# WheeStat5_1d.net
KiCad netlist of a schematic drawn in EAGLE
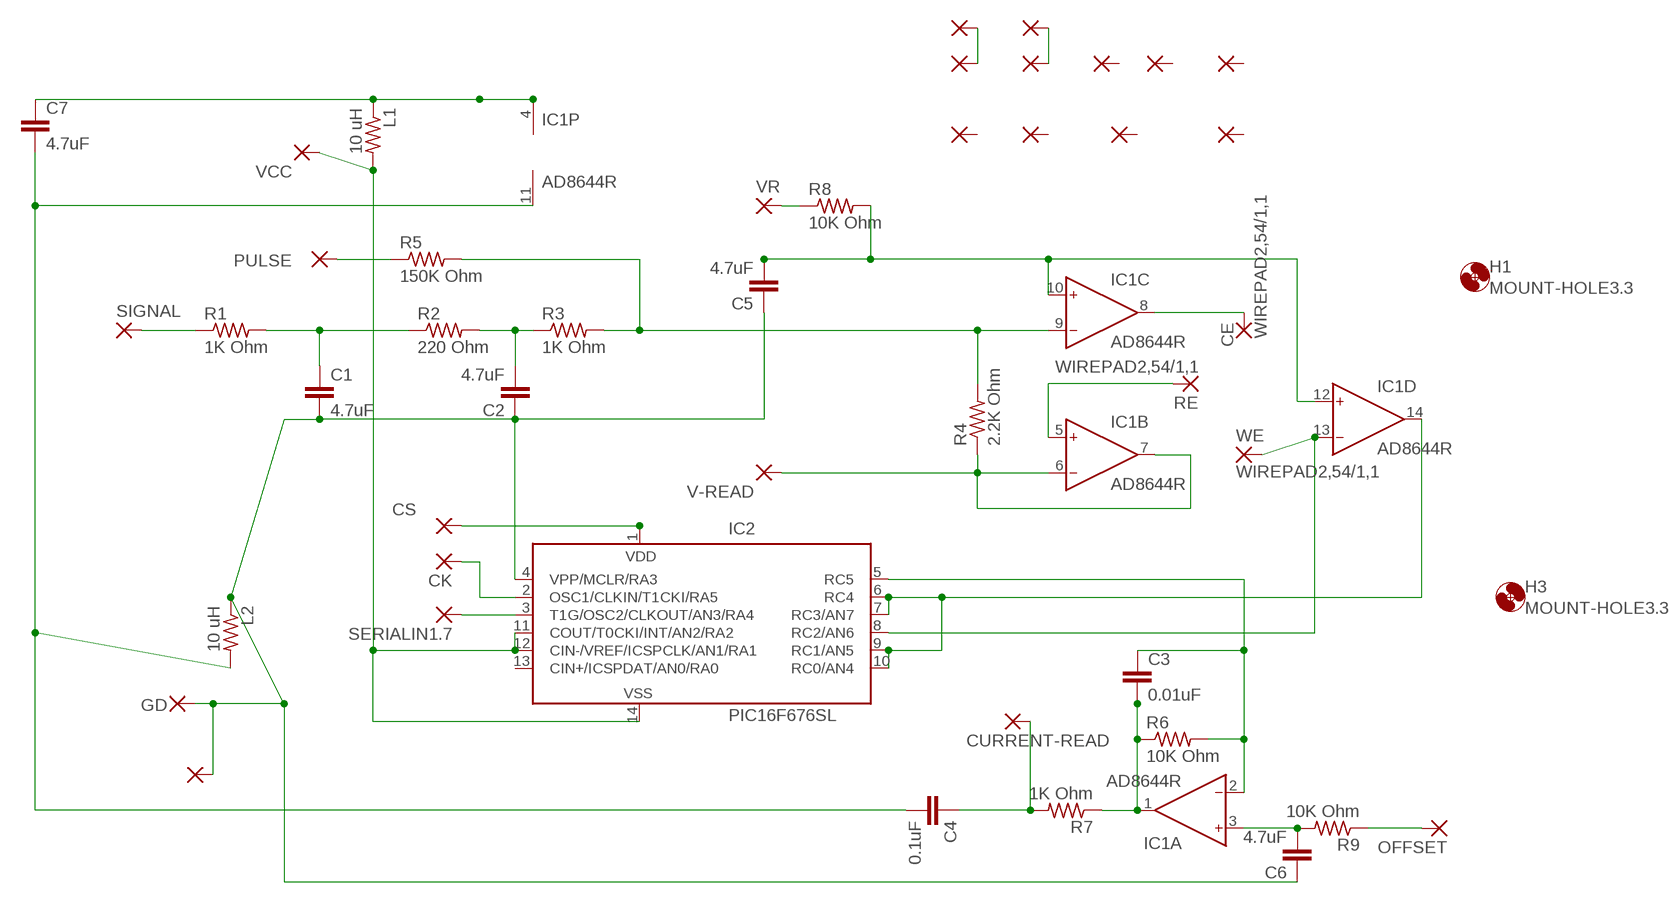
[diagram p0: schematic, sheet 1]

(export (version "E")
  (design (tool "Eeschema 10.0.6"))
  (components
    (comp (ref "1")
      (value "1,6/0,9")
      (footprint "eagle-import:1,6_0,9")
      (libsource (lib "eagle-import") (part "1,6/0,9"))
    )
    (comp (ref "1.1")
      (value "1,6/0,9")
      (footprint "eagle-import:1,6_0,9")
      (libsource (lib "eagle-import") (part "1,6/0,9"))
    )
    (comp (ref "1.2")
      (value "1,6/0,9")
      (footprint "eagle-import:1,6_0,9")
      (libsource (lib "eagle-import") (part "1,6/0,9"))
    )
    (comp (ref "1.3")
      (value "1,6/0,9")
      (footprint "eagle-import:1,6_0,9")
      (libsource (lib "eagle-import") (part "1,6/0,9"))
    )
    (comp (ref "1.4")
      (value "1,6/0,9")
      (footprint "eagle-import:1,6_0,9")
      (libsource (lib "eagle-import") (part "1,6/0,9"))
    )
    (comp (ref "2")
      (value "1,6/0,9")
      (footprint "eagle-import:1,6_0,9")
      (libsource (lib "eagle-import") (part "1,6/0,9"))
    )
    (comp (ref "3")
      (value "1,6/0,9")
      (footprint "eagle-import:1,6_0,9")
      (libsource (lib "eagle-import") (part "1,6/0,9"))
    )
    (comp (ref "4")
      (value "1,6/0,9")
      (footprint "eagle-import:1,6_0,9")
      (libsource (lib "eagle-import") (part "1,6/0,9"))
    )
    (comp (ref "5")
      (value "1,6/0,9")
      (footprint "eagle-import:1,6_0,9")
      (libsource (lib "eagle-import") (part "1,6/0,9"))
    )
    (comp (ref "6")
      (value "1,6/0,9")
      (footprint "eagle-import:1,6_0,9")
      (libsource (lib "eagle-import") (part "1,6/0,9"))
    )
    (comp (ref "7")
      (value "1,6/0,9")
      (footprint "eagle-import:1,6_0,9")
      (libsource (lib "eagle-import") (part "1,6/0,9"))
    )
    (comp (ref "8")
      (value "1,6/0,9")
      (footprint "eagle-import:1,6_0,9")
      (libsource (lib "eagle-import") (part "1,6/0,9"))
    )
    (comp (ref "C1")
      (value "4.7uF")
      (footprint "eagle-import:C1206K")
      (libsource (lib "eagle-import") (part "resistor_C-EUC1206K"))
    )
    (comp (ref "C2")
      (value "4.7uF")
      (footprint "eagle-import:C1206K")
      (libsource (lib "eagle-import") (part "resistor_C-EUC1206K"))
    )
    (comp (ref "C3")
      (value "0.01uF")
      (footprint "eagle-import:C0805")
      (libsource (lib "eagle-import") (part "C-EUC0805"))
    )
    (comp (ref "C4")
      (value "0.1uF")
      (footprint "eagle-import:C1206K")
      (libsource (lib "eagle-import") (part "resistor_C-EUC1206K"))
    )
    (comp (ref "C5")
      (value "4.7uF")
      (footprint "eagle-import:C1206K")
      (libsource (lib "eagle-import") (part "resistor_C-EUC1206K"))
    )
    (comp (ref "C6")
      (value "4.7uF")
      (footprint "eagle-import:C1206K")
      (libsource (lib "eagle-import") (part "resistor_C-EUC1206K"))
    )
    (comp (ref "C7")
      (value "4.7uF")
      (footprint "eagle-import:C1206K")
      (libsource (lib "eagle-import") (part "resistor_C-EUC1206K"))
    )
    (comp (ref "CE")
      (value "WIREPAD2,54/1,1")
      (footprint "eagle-import:2,54_1,1")
      (libsource (lib "eagle-import") (part "WIREPAD2,54/1,1"))
    )
    (comp (ref "CK")
      (value "1,6/0,9")
      (footprint "eagle-import:1,6_0,9")
      (libsource (lib "eagle-import") (part "1,6/0,9"))
    )
    (comp (ref "CS")
      (value "1,6/0,9")
      (footprint "eagle-import:1,6_0,9")
      (libsource (lib "eagle-import") (part "1,6/0,9"))
    )
    (comp (ref "CURRENT-READ")
      (value "1,6/0,9")
      (footprint "eagle-import:1,6_0,9")
      (libsource (lib "eagle-import") (part "1,6/0,9"))
    )
    (comp (ref "GD")
      (value "1,6/0,9")
      (footprint "eagle-import:1,6_0,9")
      (libsource (lib "eagle-import") (part "1,6/0,9"))
    )
    (comp (ref "H1")
      (value "MOUNT-HOLE3.3")
      (footprint "eagle-import:3,3")
      (libsource (lib "eagle-import") (part "MOUNT-HOLE3.3"))
    )
    (comp (ref "H3")
      (value "MOUNT-HOLE3.3")
      (footprint "eagle-import:3,3")
      (libsource (lib "eagle-import") (part "MOUNT-HOLE3.3"))
    )
    (comp (ref "IC1")
      (value "AD8644R")
      (footprint "eagle-import:SO14")
      (fields (field (name "MF") "ALTERA CORPORATION") (field (name "MPN") "AD8644ARZ"))
      (libsource (lib "eagle-import") (part "AD8644R"))
    )
    (comp (ref "IC2")
      (value "PIC16F676SL")
      (footprint "eagle-import:SO-14")
      (fields (field (name "MF") "MICROCHIP") (field (name "MPN") "PIC16F676-I/SL"))
      (libsource (lib "eagle-import") (part "PIC16F676SL"))
    )
    (comp (ref "L1")
      (value "10 uH")
      (footprint "eagle-import:R0805")
      (libsource (lib "eagle-import") (part "R-US_R0805"))
    )
    (comp (ref "L2")
      (value "10 uH")
      (footprint "eagle-import:R0805")
      (libsource (lib "eagle-import") (part "R-US_R0805"))
    )
    (comp (ref "OFFSET")
      (value "1,6/0,9")
      (footprint "eagle-import:1,6_0,9")
      (libsource (lib "eagle-import") (part "1,6/0,9"))
    )
    (comp (ref "PULSE")
      (value "1,6/0,9")
      (footprint "eagle-import:1,6_0,9")
      (libsource (lib "eagle-import") (part "1,6/0,9"))
    )
    (comp (ref "R1")
      (value "1K Ohm")
      (footprint "eagle-import:R0805")
      (libsource (lib "eagle-import") (part "R-US_R0805"))
    )
    (comp (ref "R2")
      (value "220 Ohm")
      (footprint "eagle-import:R0805")
      (libsource (lib "eagle-import") (part "R-US_R0805"))
    )
    (comp (ref "R3")
      (value "1K Ohm")
      (footprint "eagle-import:R0805")
      (libsource (lib "eagle-import") (part "R-US_R0805"))
    )
    (comp (ref "R4")
      (value "2.2K Ohm")
      (footprint "eagle-import:R0805")
      (libsource (lib "eagle-import") (part "R-US_R0805"))
    )
    (comp (ref "R5")
      (value "150K Ohm")
      (footprint "eagle-import:R0805")
      (libsource (lib "eagle-import") (part "R-US_R0805"))
    )
    (comp (ref "R6")
      (value "10K Ohm")
      (footprint "eagle-import:R0805")
      (libsource (lib "eagle-import") (part "R-US_R0805"))
    )
    (comp (ref "R7")
      (value "1K Ohm")
      (footprint "eagle-import:R0805")
      (libsource (lib "eagle-import") (part "R-US_R0805"))
    )
    (comp (ref "R8")
      (value "10K Ohm")
      (footprint "eagle-import:R0805")
      (libsource (lib "eagle-import") (part "R-US_R0805"))
    )
    (comp (ref "R9")
      (value "10K Ohm")
      (footprint "eagle-import:R0805")
      (libsource (lib "eagle-import") (part "R-US_R0805"))
    )
    (comp (ref "RE")
      (value "WIREPAD2,54/1,1")
      (footprint "eagle-import:2,54_1,1")
      (libsource (lib "eagle-import") (part "WIREPAD2,54/1,1"))
    )
    (comp (ref "SERIALIN1.7")
      (value "1,6/0,9")
      (footprint "eagle-import:1,6_0,9")
      (libsource (lib "eagle-import") (part "1,6/0,9"))
    )
    (comp (ref "SIGNAL")
      (value "1,6/0,9")
      (footprint "eagle-import:1,6_0,9")
      (libsource (lib "eagle-import") (part "1,6/0,9"))
    )
    (comp (ref "V-READ")
      (value "1,6/0,9")
      (footprint "eagle-import:1,6_0,9")
      (libsource (lib "eagle-import") (part "1,6/0,9"))
    )
    (comp (ref "VCC")
      (value "1,6/0,9")
      (footprint "eagle-import:1,6_0,9")
      (libsource (lib "eagle-import") (part "1,6/0,9"))
    )
    (comp (ref "VR")
      (value "1,6/0,9")
      (footprint "eagle-import:1,6_0,9")
      (libsource (lib "eagle-import") (part "1,6/0,9"))
    )
    (comp (ref "WE")
      (value "WIREPAD2,54/1,1")
      (footprint "eagle-import:2,54_1,1")
      (libsource (lib "eagle-import") (part "WIREPAD2,54/1,1"))
    )
  )
  (nets
    (net (code "1") (name "Net-(1.1-P)") (class "Default")
      (node (ref "1.1") (pin "1") (pinfunction "P_1") (pintype "passive"))
      (node (ref "C1") (pin "2") (pinfunction "2_2") (pintype "passive"))
      (node (ref "C2") (pin "1") (pinfunction "1_1") (pintype "passive"))
      (node (ref "C5") (pin "1") (pinfunction "1_1") (pintype "passive"))
      (node (ref "C6") (pin "1") (pinfunction "1_1") (pintype "passive"))
      (node (ref "GD") (pin "1") (pinfunction "P_1") (pintype "passive"))
      (node (ref "IC2") (pin "4") (pinfunction "VPP/MCLR/RA3_4") (pintype "input"))
      (node (ref "L2") (pin "1") (pinfunction "1_1") (pintype "passive"))
    )
    (net (code "2") (name "Net-(1.2-P)") (class "Default")
      (node (ref "1.2") (pin "1") (pinfunction "P_1") (pintype "passive"))
      (node (ref "1.3") (pin "1") (pinfunction "P_1") (pintype "passive"))
    )
    (net (code "3") (name "Net-(1.4-P)") (class "Default")
      (node (ref "1.4") (pin "1") (pinfunction "P_1") (pintype "passive"))
      (node (ref "8") (pin "1") (pinfunction "P_1") (pintype "passive"))
    )
    (net (code "4") (name "Net-(C1-Pad1)") (class "Default")
      (node (ref "C1") (pin "1") (pinfunction "1_1") (pintype "passive"))
      (node (ref "R1") (pin "2") (pinfunction "2_2") (pintype "passive"))
      (node (ref "R2") (pin "1") (pinfunction "1_1") (pintype "passive"))
    )
    (net (code "5") (name "Net-(C2-Pad2)") (class "Default")
      (node (ref "C2") (pin "2") (pinfunction "2_2") (pintype "passive"))
      (node (ref "R2") (pin "2") (pinfunction "2_2") (pintype "passive"))
      (node (ref "R3") (pin "1") (pinfunction "1_1") (pintype "passive"))
    )
    (net (code "6") (name "Net-(CE-P)") (class "Default")
      (node (ref "CE") (pin "1") (pinfunction "P_1") (pintype "passive"))
      (node (ref "IC1") (pin "8") (pinfunction "OUT_8") (pintype "output"))
    )
    (net (code "7") (name "Net-(CK-P)") (class "Default")
      (node (ref "CK") (pin "1") (pinfunction "P_1") (pintype "passive"))
      (node (ref "IC2") (pin "2") (pinfunction "OSC1/CLKIN/T1CKI/RA5_2") (pintype "bidirectional"))
    )
    (net (code "8") (name "Net-(CS-P)") (class "Default")
      (node (ref "CS") (pin "1") (pinfunction "P_1") (pintype "passive"))
      (node (ref "IC2") (pin "1") (pinfunction "VDD_1") (pintype "power_in"))
    )
    (net (code "9") (name "Net-(CURRENT-READ-P)") (class "Default")
      (node (ref "C4") (pin "1") (pinfunction "1_1") (pintype "passive"))
      (node (ref "CURRENT-READ") (pin "1") (pinfunction "P_1") (pintype "passive"))
      (node (ref "R7") (pin "2") (pinfunction "2_2") (pintype "passive"))
    )
    (net (code "10") (name "Net-(IC1A-IN+)") (class "Default")
      (node (ref "C6") (pin "2") (pinfunction "2_2") (pintype "passive"))
      (node (ref "IC1") (pin "3") (pinfunction "IN+_3") (pintype "input"))
      (node (ref "R9") (pin "2") (pinfunction "2_2") (pintype "passive"))
    )
    (net (code "11") (name "Net-(IC1A-IN-)") (class "Default")
      (node (ref "C3") (pin "1") (pinfunction "1_1") (pintype "passive"))
      (node (ref "IC1") (pin "2") (pinfunction "IN-_2") (pintype "input"))
      (node (ref "IC2") (pin "5") (pinfunction "RC5_5") (pintype "bidirectional"))
      (node (ref "R6") (pin "2") (pinfunction "2_2") (pintype "passive"))
    )
    (net (code "12") (name "Net-(IC1A-OUT)") (class "Default")
      (node (ref "C3") (pin "2") (pinfunction "2_2") (pintype "passive"))
      (node (ref "IC1") (pin "1") (pinfunction "OUT_1") (pintype "output"))
      (node (ref "R6") (pin "1") (pinfunction "1_1") (pintype "passive"))
      (node (ref "R7") (pin "1") (pinfunction "1_1") (pintype "passive"))
    )
    (net (code "13") (name "Net-(IC1B-IN+)") (class "Default")
      (node (ref "IC1") (pin "5") (pinfunction "IN+_5") (pintype "input"))
      (node (ref "RE") (pin "1") (pinfunction "P_1") (pintype "passive"))
    )
    (net (code "14") (name "Net-(IC1B-IN-)") (class "Default")
      (node (ref "IC1") (pin "6") (pinfunction "IN-_6") (pintype "input"))
      (node (ref "IC1") (pin "7") (pinfunction "OUT_7") (pintype "output"))
      (node (ref "R4") (pin "1") (pinfunction "1_1") (pintype "passive"))
      (node (ref "V-READ") (pin "1") (pinfunction "P_1") (pintype "passive"))
    )
    (net (code "15") (name "Net-(IC1C-IN+)") (class "Default")
      (node (ref "C5") (pin "2") (pinfunction "2_2") (pintype "passive"))
      (node (ref "IC1") (pin "10") (pinfunction "IN+_10") (pintype "input"))
      (node (ref "IC1") (pin "12") (pinfunction "IN+_12") (pintype "input"))
      (node (ref "R8") (pin "2") (pinfunction "2_2") (pintype "passive"))
    )
    (net (code "16") (name "Net-(IC1C-IN-)") (class "Default")
      (node (ref "IC1") (pin "9") (pinfunction "IN-_9") (pintype "input"))
      (node (ref "R3") (pin "2") (pinfunction "2_2") (pintype "passive"))
      (node (ref "R4") (pin "2") (pinfunction "2_2") (pintype "passive"))
      (node (ref "R5") (pin "2") (pinfunction "2_2") (pintype "passive"))
    )
    (net (code "17") (name "Net-(IC1D-IN-)") (class "Default")
      (node (ref "IC1") (pin "13") (pinfunction "IN-_13") (pintype "input"))
      (node (ref "IC2") (pin "8") (pinfunction "RC2/AN6_8") (pintype "bidirectional"))
      (node (ref "WE") (pin "1") (pinfunction "P_1") (pintype "passive"))
    )
    (net (code "18") (name "Net-(IC1D-OUT)") (class "Default")
      (node (ref "IC1") (pin "14") (pinfunction "OUT_14") (pintype "output"))
      (node (ref "IC2") (pin "10") (pinfunction "RC0/AN4_10") (pintype "bidirectional"))
      (node (ref "IC2") (pin "6") (pinfunction "RC4_6") (pintype "bidirectional"))
      (node (ref "IC2") (pin "7") (pinfunction "RC3/AN7_7") (pintype "bidirectional"))
      (node (ref "IC2") (pin "9") (pinfunction "RC1/AN5_9") (pintype "bidirectional"))
    )
    (net (code "19") (name "Net-(IC1E-V+)") (class "Default")
      (node (ref "C7") (pin "1") (pinfunction "1_1") (pintype "passive"))
      (node (ref "IC1") (pin "4") (pinfunction "V+_4") (pintype "power_in"))
      (node (ref "L1") (pin "1") (pinfunction "1_1") (pintype "passive"))
    )
    (net (code "20") (name "Net-(IC1E-V-)") (class "Default")
      (node (ref "C4") (pin "2") (pinfunction "2_2") (pintype "passive"))
      (node (ref "C7") (pin "2") (pinfunction "2_2") (pintype "passive"))
      (node (ref "IC1") (pin "11") (pinfunction "V-_11") (pintype "power_in"))
      (node (ref "L2") (pin "2") (pinfunction "2_2") (pintype "passive"))
    )
    (net (code "21") (name "Net-(IC2-CIN-{slash}VREF{slash}ICSPCLK{slash}AN1{slash}RA1)") (class "Default")
      (node (ref "IC2") (pin "11") (pinfunction "COUT/T0CKI/INT/AN2/RA2_11") (pintype "bidirectional"))
      (node (ref "IC2") (pin "12") (pinfunction "CIN-/VREF/ICSPCLK/AN1/RA1_12") (pintype "bidirectional"))
      (node (ref "IC2") (pin "14") (pinfunction "VSS_14") (pintype "power_in"))
      (node (ref "L1") (pin "2") (pinfunction "2_2") (pintype "passive"))
      (node (ref "VCC") (pin "1") (pinfunction "P_1") (pintype "passive"))
    )
    (net (code "22") (name "Net-(IC2-T1G{slash}OSC2{slash}CLKOUT{slash}AN3{slash}RA4)") (class "Default")
      (node (ref "IC2") (pin "3") (pinfunction "T1G/OSC2/CLKOUT/AN3/RA4_3") (pintype "bidirectional"))
      (node (ref "SERIALIN1.7") (pin "1") (pinfunction "P_1") (pintype "passive"))
    )
    (net (code "23") (name "Net-(OFFSET-P)") (class "Default")
      (node (ref "OFFSET") (pin "1") (pinfunction "P_1") (pintype "passive"))
      (node (ref "R9") (pin "1") (pinfunction "1_1") (pintype "passive"))
    )
    (net (code "24") (name "Net-(PULSE-P)") (class "Default")
      (node (ref "PULSE") (pin "1") (pinfunction "P_1") (pintype "passive"))
      (node (ref "R5") (pin "1") (pinfunction "1_1") (pintype "passive"))
    )
    (net (code "25") (name "Net-(SIGNAL-P)") (class "Default")
      (node (ref "R1") (pin "1") (pinfunction "1_1") (pintype "passive"))
      (node (ref "SIGNAL") (pin "1") (pinfunction "P_1") (pintype "passive"))
    )
    (net (code "26") (name "Net-(VR-P)") (class "Default")
      (node (ref "R8") (pin "1") (pinfunction "1_1") (pintype "passive"))
      (node (ref "VR") (pin "1") (pinfunction "P_1") (pintype "passive"))
    )
    (net (code "27") (name "unconnected-(1-P-Pad1)") (class "Default")
      (node (ref "1") (pin "1") (pinfunction "P_1") (pintype "passive"))
    )
    (net (code "28") (name "unconnected-(2-P-Pad1)") (class "Default")
      (node (ref "2") (pin "1") (pinfunction "P_1") (pintype "passive"))
    )
    (net (code "29") (name "unconnected-(3-P-Pad1)") (class "Default")
      (node (ref "3") (pin "1") (pinfunction "P_1") (pintype "passive"))
    )
    (net (code "30") (name "unconnected-(4-P-Pad1)") (class "Default")
      (node (ref "4") (pin "1") (pinfunction "P_1") (pintype "passive"))
    )
    (net (code "31") (name "unconnected-(5-P-Pad1)") (class "Default")
      (node (ref "5") (pin "1") (pinfunction "P_1") (pintype "passive"))
    )
    (net (code "32") (name "unconnected-(6-P-Pad1)") (class "Default")
      (node (ref "6") (pin "1") (pinfunction "P_1") (pintype "passive"))
    )
    (net (code "33") (name "unconnected-(7-P-Pad1)") (class "Default")
      (node (ref "7") (pin "1") (pinfunction "P_1") (pintype "passive"))
    )
    (net (code "34") (name "unconnected-(IC2-CIN+{slash}ICSPDAT{slash}AN0{slash}RA0-Pad13)") (class "Default")
      (node (ref "IC2") (pin "13") (pinfunction "CIN+/ICSPDAT/AN0/RA0_13") (pintype "bidirectional"))
    )
  )
)
